# LMNC_VCO_-_v1_2.net
KiCad netlist of a schematic drawn in EAGLE
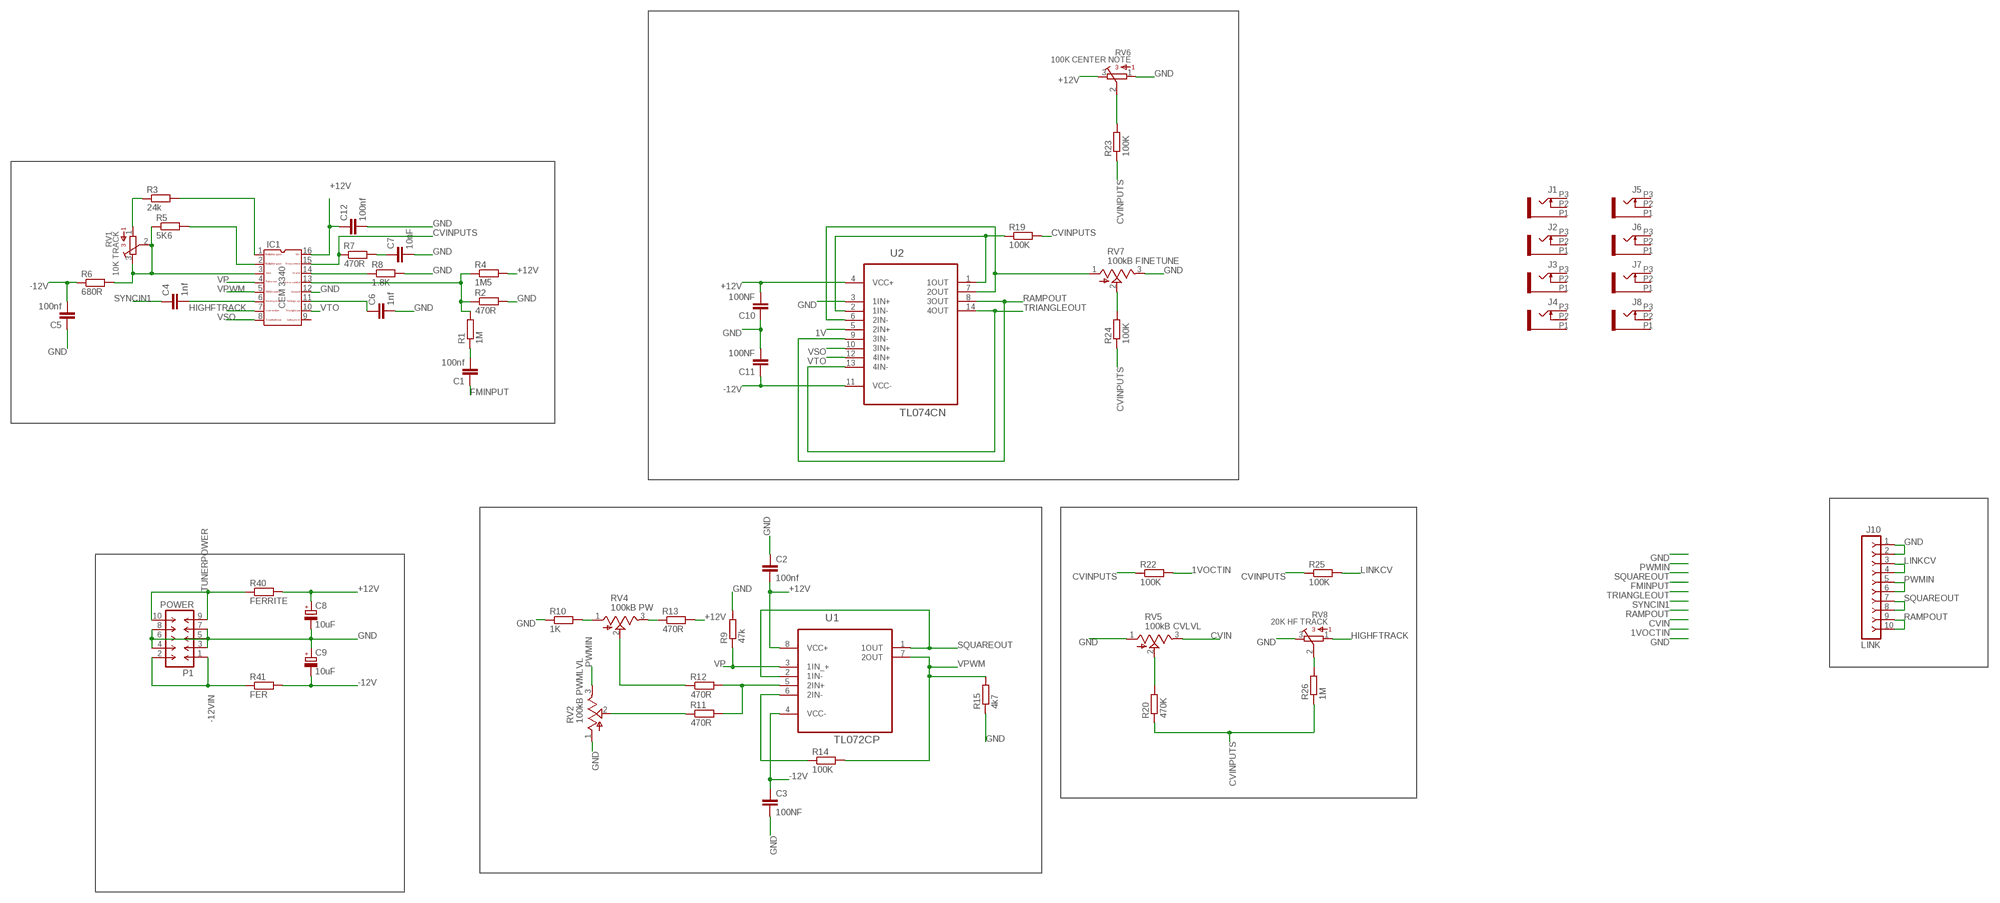
[diagram p0: schematic, sheet 1]

(export (version "E")
  (design (tool "Eeschema 10.0.6"))
  (components
    (comp (ref "C1")
      (value "100nf")
      (footprint "eagle-import:C0603")
      (libsource (lib "eagle-import") (part "C-EUC0603"))
    )
    (comp (ref "C2")
      (value "100nf")
      (footprint "eagle-import:C0603")
      (libsource (lib "eagle-import") (part "C-EUC0603"))
    )
    (comp (ref "C3")
      (value "100NF")
      (footprint "eagle-import:C0603")
      (libsource (lib "eagle-import") (part "C-EUC0603"))
    )
    (comp (ref "C4")
      (value "1nf")
      (footprint "eagle-import:C0603")
      (libsource (lib "eagle-import") (part "C-EUC0603"))
    )
    (comp (ref "C5")
      (value "100nf")
      (footprint "eagle-import:C0603")
      (libsource (lib "eagle-import") (part "C-EUC0603"))
    )
    (comp (ref "C6")
      (value "1nf")
      (footprint "eagle-import:C0603")
      (libsource (lib "eagle-import") (part "C-EUC0603"))
    )
    (comp (ref "C7")
      (value "10nF")
      (footprint "eagle-import:C0603")
      (libsource (lib "eagle-import") (part "C-EUC0603"))
    )
    (comp (ref "C8")
      (value "10uF")
      (footprint "eagle-import:153CLV-0605")
      (libsource (lib "eagle-import") (part "CPOL-EU153CLV-0605"))
    )
    (comp (ref "C9")
      (value "10uF")
      (footprint "eagle-import:153CLV-0605")
      (libsource (lib "eagle-import") (part "CPOL-EU153CLV-0605"))
    )
    (comp (ref "C10")
      (value "100NF")
      (footprint "eagle-import:C0603")
      (libsource (lib "eagle-import") (part "C-EUC0603"))
    )
    (comp (ref "C11")
      (value "100NF")
      (footprint "eagle-import:C0603")
      (libsource (lib "eagle-import") (part "C-EUC0603"))
    )
    (comp (ref "C12")
      (value "100nf")
      (footprint "eagle-import:C0603")
      (libsource (lib "eagle-import") (part "C-EUC0603"))
    )
    (comp (ref "IC1")
      (value "CEM3340")
      (footprint "eagle-import:DIL16")
      (libsource (lib "eagle-import") (part "CEM3340"))
    )
    (comp (ref "J1")
      (value "PJ301_THONKICONNTME")
      (footprint "eagle-import:WQP_PJ_301M_TME")
      (libsource (lib "eagle-import") (part "PJ301_THONKICONNTME"))
    )
    (comp (ref "J2")
      (value "PJ301_THONKICONNTME")
      (footprint "eagle-import:WQP_PJ_301M_TME")
      (libsource (lib "eagle-import") (part "PJ301_THONKICONNTME"))
    )
    (comp (ref "J3")
      (value "PJ301_THONKICONNTME")
      (footprint "eagle-import:WQP_PJ_301M_TME")
      (libsource (lib "eagle-import") (part "PJ301_THONKICONNTME"))
    )
    (comp (ref "J4")
      (value "PJ301_THONKICONNTME")
      (footprint "eagle-import:WQP_PJ_301M_TME")
      (libsource (lib "eagle-import") (part "PJ301_THONKICONNTME"))
    )
    (comp (ref "J5")
      (value "PJ301_THONKICONNTME")
      (footprint "eagle-import:WQP_PJ_301M_TME")
      (libsource (lib "eagle-import") (part "PJ301_THONKICONNTME"))
    )
    (comp (ref "J6")
      (value "PJ301_THONKICONNTME")
      (footprint "eagle-import:WQP_PJ_301M_TME")
      (libsource (lib "eagle-import") (part "PJ301_THONKICONNTME"))
    )
    (comp (ref "J7")
      (value "PJ301_THONKICONNTME")
      (footprint "eagle-import:WQP_PJ_301M_TME")
      (libsource (lib "eagle-import") (part "PJ301_THONKICONNTME"))
    )
    (comp (ref "J8")
      (value "PJ301_THONKICONNTME")
      (footprint "eagle-import:WQP_PJ_301M_TME")
      (libsource (lib "eagle-import") (part "PJ301_THONKICONNTME"))
    )
    (comp (ref "J10")
      (value "LINK")
      (footprint "eagle-import:SIP-100-10-32Y")
      (libsource (lib "eagle-import") (part "F-1X10-SIP-100-32Y"))
    )
    (comp (ref "P1")
      (value "POWER")
      (footprint "eagle-import:DIL-100-2X05")
      (libsource (lib "eagle-import") (part "M-2X05-DIL-100"))
    )
    (comp (ref "R1")
      (value "1M")
      (footprint "eagle-import:R0603")
      (libsource (lib "eagle-import") (part "R-EU_R0603"))
    )
    (comp (ref "R2")
      (value "470R")
      (footprint "eagle-import:R0603")
      (libsource (lib "eagle-import") (part "R-EU_R0603"))
    )
    (comp (ref "R3")
      (value "24k")
      (footprint "eagle-import:R0603")
      (libsource (lib "eagle-import") (part "R-EU_R0603"))
    )
    (comp (ref "R4")
      (value "1M5")
      (footprint "eagle-import:R0603")
      (libsource (lib "eagle-import") (part "R-EU_R0603"))
    )
    (comp (ref "R5")
      (value "5K6")
      (footprint "eagle-import:R0603")
      (libsource (lib "eagle-import") (part "R-EU_R0603"))
    )
    (comp (ref "R6")
      (value "680R")
      (footprint "eagle-import:R0603")
      (libsource (lib "eagle-import") (part "R-EU_R0603"))
    )
    (comp (ref "R7")
      (value "470R")
      (footprint "eagle-import:R0603")
      (libsource (lib "eagle-import") (part "R-EU_R0603"))
    )
    (comp (ref "R8")
      (value "1.8K")
      (footprint "eagle-import:R0603")
      (libsource (lib "eagle-import") (part "R-EU_R0603"))
    )
    (comp (ref "R9")
      (value "47k")
      (footprint "eagle-import:R0603")
      (libsource (lib "eagle-import") (part "R-EU_R0603"))
    )
    (comp (ref "R10")
      (value "1K")
      (footprint "eagle-import:R0603")
      (libsource (lib "eagle-import") (part "R-EU_R0603"))
    )
    (comp (ref "R11")
      (value "470R")
      (footprint "eagle-import:R0603")
      (libsource (lib "eagle-import") (part "R-EU_R0603"))
    )
    (comp (ref "R12")
      (value "470R")
      (footprint "eagle-import:R0603")
      (libsource (lib "eagle-import") (part "R-EU_R0603"))
    )
    (comp (ref "R13")
      (value "470R")
      (footprint "eagle-import:R0603")
      (libsource (lib "eagle-import") (part "R-EU_R0603"))
    )
    (comp (ref "R14")
      (value "100K")
      (footprint "eagle-import:R0603")
      (libsource (lib "eagle-import") (part "R-EU_R0603"))
    )
    (comp (ref "R15")
      (value "4k7")
      (footprint "eagle-import:R0603")
      (libsource (lib "eagle-import") (part "R-EU_R0603"))
    )
    (comp (ref "R19")
      (value "100K")
      (footprint "eagle-import:R0603")
      (libsource (lib "eagle-import") (part "R-EU_R0603"))
    )
    (comp (ref "R20")
      (value "470K")
      (footprint "eagle-import:R0603")
      (libsource (lib "eagle-import") (part "R-EU_R0603"))
    )
    (comp (ref "R22")
      (value "100K")
      (footprint "eagle-import:R0603")
      (libsource (lib "eagle-import") (part "R-EU_R0603"))
    )
    (comp (ref "R23")
      (value "100K")
      (footprint "eagle-import:R0603")
      (libsource (lib "eagle-import") (part "R-EU_R0603"))
    )
    (comp (ref "R24")
      (value "100K")
      (footprint "eagle-import:R0603")
      (libsource (lib "eagle-import") (part "R-EU_R0603"))
    )
    (comp (ref "R25")
      (value "100K")
      (footprint "eagle-import:R0603")
      (libsource (lib "eagle-import") (part "R-EU_R0603"))
    )
    (comp (ref "R26")
      (value "1M")
      (footprint "eagle-import:R0603")
      (libsource (lib "eagle-import") (part "R-EU_R0603"))
    )
    (comp (ref "R40")
      (value "FERRITE")
      (footprint "eagle-import:R0603")
      (libsource (lib "eagle-import") (part "R-EU_R0603"))
    )
    (comp (ref "R41")
      (value "FER")
      (footprint "eagle-import:R0603")
      (libsource (lib "eagle-import") (part "R-EU_R0603"))
    )
    (comp (ref "RV1")
      (value "10K TRACK")
      (footprint "eagle-import:3386W")
      (libsource (lib "eagle-import") (part "3386-W"))
    )
    (comp (ref "RV2")
      (value "100kB PWMLVL")
      (footprint "eagle-import:ALPS_POT_VERTICAL")
      (libsource (lib "eagle-import") (part "POT_VERTICAL"))
    )
    (comp (ref "RV4")
      (value "100kB PW")
      (footprint "eagle-import:ALPS_POT_VERTICAL")
      (libsource (lib "eagle-import") (part "POT_VERTICAL"))
    )
    (comp (ref "RV5")
      (value "100kB CVLVL")
      (footprint "eagle-import:ALPS_POT_VERTICAL")
      (libsource (lib "eagle-import") (part "POT_VERTICAL"))
    )
    (comp (ref "RV6")
      (value "100K CENTER NOTE")
      (footprint "eagle-import:3386W")
      (libsource (lib "eagle-import") (part "3386-W"))
    )
    (comp (ref "RV7")
      (value "100kB FINETUNE")
      (footprint "eagle-import:ALPS_POT_VERTICAL")
      (libsource (lib "eagle-import") (part "POT_VERTICAL"))
    )
    (comp (ref "RV8")
      (value "20K HF TRACK")
      (footprint "eagle-import:3386W")
      (libsource (lib "eagle-import") (part "3386-W"))
    )
    (comp (ref "U1")
      (value "TL072CP")
      (footprint "eagle-import:DIP254P762X508-8")
      (fields (field (name "MF") "Texas Instruments"))
      (libsource (lib "eagle-import") (part "TL072CP"))
    )
    (comp (ref "U2")
      (value "TL074CN")
      (footprint "eagle-import:DIP254P762X508-14")
      (fields (field (name "MF") "STMicroelectronics"))
      (libsource (lib "eagle-import") (part "TL074CN"))
    )
  )
  (nets
    (net (code "1") (name "+12V") (class "Default")
      (node (ref "C10") (pin "2") (pinfunction "2_2") (pintype "passive"))
      (node (ref "C12") (pin "1") (pinfunction "1_1") (pintype "passive"))
      (node (ref "C2") (pin "2") (pinfunction "2_2") (pintype "passive"))
      (node (ref "C8") (pin "+") (pinfunction "+_+") (pintype "passive"))
      (node (ref "IC1") (pin "16") (pinfunction "16_16") (pintype "power_in"))
      (node (ref "R13") (pin "2") (pinfunction "2_2") (pintype "passive"))
      (node (ref "R4") (pin "2") (pinfunction "2_2") (pintype "passive"))
      (node (ref "R40") (pin "2") (pinfunction "2_2") (pintype "passive"))
      (node (ref "RV6") (pin "3") (pinfunction "3_3") (pintype "passive"))
      (node (ref "U1") (pin "8") (pinfunction "VCC+_8") (pintype "power_in"))
      (node (ref "U2") (pin "4") (pinfunction "VCC+_4") (pintype "power_in"))
    )
    (net (code "2") (name "-12V") (class "Default")
      (node (ref "C11") (pin "1") (pinfunction "1_1") (pintype "passive"))
      (node (ref "C3") (pin "1") (pinfunction "1_1") (pintype "passive"))
      (node (ref "C5") (pin "2") (pinfunction "2_2") (pintype "passive"))
      (node (ref "C9") (pin "-") (pinfunction "-_-") (pintype "passive"))
      (node (ref "R41") (pin "2") (pinfunction "2_2") (pintype "passive"))
      (node (ref "R6") (pin "1") (pinfunction "1_1") (pintype "passive"))
      (node (ref "U1") (pin "4") (pinfunction "VCC-_4") (pintype "passive"))
      (node (ref "U2") (pin "11") (pinfunction "VCC-_11") (pintype "power_in"))
    )
    (net (code "3") (name "-12VIN") (class "Default")
      (node (ref "P1") (pin "1") (pinfunction "1_1") (pintype "passive"))
      (node (ref "P1") (pin "2") (pinfunction "2_2") (pintype "passive"))
      (node (ref "R41") (pin "1") (pinfunction "1_1") (pintype "passive"))
    )
    (net (code "4") (name "1V") (class "Default")
      (node (ref "U2") (pin "5") (pinfunction "2IN+_5") (pintype "input"))
    )
    (net (code "5") (name "1VOCTIN") (class "Default")
      (node (ref "R22") (pin "2") (pinfunction "2_2") (pintype "passive"))
    )
    (net (code "6") (name "CVIN") (class "Default")
      (node (ref "RV5") (pin "3") (pinfunction "B_3") (pintype "passive"))
    )
    (net (code "7") (name "CVINPUTS") (class "Default")
      (node (ref "IC1") (pin "15") (pinfunction "15_15") (pintype "input"))
      (node (ref "R19") (pin "2") (pinfunction "2_2") (pintype "passive"))
      (node (ref "R20") (pin "1") (pinfunction "1_1") (pintype "passive"))
      (node (ref "R22") (pin "1") (pinfunction "1_1") (pintype "passive"))
      (node (ref "R23") (pin "1") (pinfunction "1_1") (pintype "passive"))
      (node (ref "R24") (pin "1") (pinfunction "1_1") (pintype "passive"))
      (node (ref "R25") (pin "1") (pinfunction "1_1") (pintype "passive"))
      (node (ref "R26") (pin "1") (pinfunction "1_1") (pintype "passive"))
      (node (ref "R7") (pin "1") (pinfunction "1_1") (pintype "passive"))
    )
    (net (code "8") (name "FMINPUT") (class "Default")
      (node (ref "C1") (pin "1") (pinfunction "1_1") (pintype "passive"))
    )
    (net (code "9") (name "GND") (class "Default")
      (node (ref "C10") (pin "1") (pinfunction "1_1") (pintype "passive"))
      (node (ref "C11") (pin "2") (pinfunction "2_2") (pintype "passive"))
      (node (ref "C12") (pin "2") (pinfunction "2_2") (pintype "passive"))
      (node (ref "C2") (pin "1") (pinfunction "1_1") (pintype "passive"))
      (node (ref "C3") (pin "2") (pinfunction "2_2") (pintype "passive"))
      (node (ref "C5") (pin "1") (pinfunction "1_1") (pintype "passive"))
      (node (ref "C6") (pin "2") (pinfunction "2_2") (pintype "passive"))
      (node (ref "C7") (pin "2") (pinfunction "2_2") (pintype "passive"))
      (node (ref "C8") (pin "-") (pinfunction "-_-") (pintype "passive"))
      (node (ref "C9") (pin "+") (pinfunction "+_+") (pintype "passive"))
      (node (ref "IC1") (pin "12") (pinfunction "12_12") (pintype "power_in"))
      (node (ref "J10") (pin "1") (pinfunction "1_1") (pintype "passive"))
      (node (ref "J10") (pin "2") (pinfunction "2_2") (pintype "passive"))
      (node (ref "P1") (pin "3") (pinfunction "3_3") (pintype "passive"))
      (node (ref "P1") (pin "4") (pinfunction "4_4") (pintype "passive"))
      (node (ref "P1") (pin "5") (pinfunction "5_5") (pintype "passive"))
      (node (ref "P1") (pin "6") (pinfunction "6_6") (pintype "passive"))
      (node (ref "P1") (pin "7") (pinfunction "7_7") (pintype "passive"))
      (node (ref "P1") (pin "8") (pinfunction "8_8") (pintype "passive"))
      (node (ref "R10") (pin "1") (pinfunction "1_1") (pintype "passive"))
      (node (ref "R15") (pin "1") (pinfunction "1_1") (pintype "passive"))
      (node (ref "R2") (pin "2") (pinfunction "2_2") (pintype "passive"))
      (node (ref "R8") (pin "2") (pinfunction "2_2") (pintype "passive"))
      (node (ref "R9") (pin "2") (pinfunction "2_2") (pintype "passive"))
      (node (ref "RV2") (pin "1") (pinfunction "A_1") (pintype "passive"))
      (node (ref "RV5") (pin "1") (pinfunction "A_1") (pintype "passive"))
      (node (ref "RV6") (pin "1") (pinfunction "1_1") (pintype "passive"))
      (node (ref "RV7") (pin "3") (pinfunction "B_3") (pintype "passive"))
      (node (ref "RV8") (pin "3") (pinfunction "3_3") (pintype "passive"))
      (node (ref "U2") (pin "3") (pinfunction "1IN+_3") (pintype "input"))
    )
    (net (code "10") (name "HIGHFTRACK") (class "Default")
      (node (ref "IC1") (pin "7") (pinfunction "7_7") (pintype "bidirectional"))
      (node (ref "RV8") (pin "1") (pinfunction "1_1") (pintype "passive"))
    )
    (net (code "11") (name "LINKCV") (class "Default")
      (node (ref "J10") (pin "3") (pinfunction "3_3") (pintype "passive"))
      (node (ref "J10") (pin "4") (pinfunction "4_4") (pintype "passive"))
      (node (ref "R25") (pin "2") (pinfunction "2_2") (pintype "passive"))
    )
    (net (code "12") (name "Net-(C1-Pad2)") (class "Default")
      (node (ref "C1") (pin "2") (pinfunction "2_2") (pintype "passive"))
      (node (ref "R1") (pin "1") (pinfunction "1_1") (pintype "passive"))
    )
    (net (code "13") (name "Net-(C4-Pad2)") (class "Default")
      (node (ref "C4") (pin "2") (pinfunction "2_2") (pintype "passive"))
      (node (ref "IC1") (pin "6") (pinfunction "6_6") (pintype "input"))
    )
    (net (code "14") (name "Net-(C6-Pad1)") (class "Default")
      (node (ref "C6") (pin "1") (pinfunction "1_1") (pintype "passive"))
      (node (ref "IC1") (pin "11") (pinfunction "11_11") (pintype "bidirectional"))
    )
    (net (code "15") (name "Net-(C7-Pad1)") (class "Default")
      (node (ref "C7") (pin "1") (pinfunction "1_1") (pintype "passive"))
      (node (ref "R7") (pin "2") (pinfunction "2_2") (pintype "passive"))
    )
    (net (code "16") (name "Net-(IC1-Pad1)") (class "Default")
      (node (ref "IC1") (pin "1") (pinfunction "1_1") (pintype "bidirectional"))
      (node (ref "R3") (pin "2") (pinfunction "2_2") (pintype "passive"))
    )
    (net (code "17") (name "Net-(IC1-Pad2)") (class "Default")
      (node (ref "IC1") (pin "2") (pinfunction "2_2") (pintype "bidirectional"))
      (node (ref "R5") (pin "2") (pinfunction "2_2") (pintype "passive"))
    )
    (net (code "18") (name "Net-(IC1-Pad3)") (class "Default")
      (node (ref "IC1") (pin "3") (pinfunction "3_3") (pintype "power_in"))
      (node (ref "R5") (pin "1") (pinfunction "1_1") (pintype "passive"))
      (node (ref "R6") (pin "2") (pinfunction "2_2") (pintype "passive"))
      (node (ref "RV1") (pin "2") (pinfunction "2_2") (pintype "passive"))
      (node (ref "RV1") (pin "3") (pinfunction "3_3") (pintype "passive"))
    )
    (net (code "19") (name "Net-(IC1-Pad13)") (class "Default")
      (node (ref "IC1") (pin "13") (pinfunction "13_13") (pintype "input"))
      (node (ref "R1") (pin "2") (pinfunction "2_2") (pintype "passive"))
      (node (ref "R2") (pin "1") (pinfunction "1_1") (pintype "passive"))
      (node (ref "R4") (pin "1") (pinfunction "1_1") (pintype "passive"))
    )
    (net (code "20") (name "Net-(IC1-Pad14)") (class "Default")
      (node (ref "IC1") (pin "14") (pinfunction "14_14") (pintype "input"))
      (node (ref "R8") (pin "1") (pinfunction "1_1") (pintype "passive"))
    )
    (net (code "21") (name "Net-(R3-Pad1)") (class "Default")
      (node (ref "R3") (pin "1") (pinfunction "1_1") (pintype "passive"))
      (node (ref "RV1") (pin "1") (pinfunction "1_1") (pintype "passive"))
    )
    (net (code "22") (name "Net-(R23-Pad2)") (class "Default")
      (node (ref "R23") (pin "2") (pinfunction "2_2") (pintype "passive"))
      (node (ref "RV6") (pin "2") (pinfunction "2_2") (pintype "passive"))
    )
    (net (code "23") (name "Net-(R26-Pad2)") (class "Default")
      (node (ref "R26") (pin "2") (pinfunction "2_2") (pintype "passive"))
      (node (ref "RV8") (pin "2") (pinfunction "2_2") (pintype "passive"))
    )
    (net (code "24") (name "Net-(RV2-W)") (class "Default")
      (node (ref "R11") (pin "1") (pinfunction "1_1") (pintype "passive"))
      (node (ref "RV2") (pin "2") (pinfunction "W_2") (pintype "passive"))
    )
    (net (code "25") (name "Net-(RV4-A)") (class "Default")
      (node (ref "R10") (pin "2") (pinfunction "2_2") (pintype "passive"))
      (node (ref "RV4") (pin "1") (pinfunction "A_1") (pintype "passive"))
    )
    (net (code "26") (name "Net-(RV4-B)") (class "Default")
      (node (ref "R13") (pin "1") (pinfunction "1_1") (pintype "passive"))
      (node (ref "RV4") (pin "3") (pinfunction "B_3") (pintype "passive"))
    )
    (net (code "27") (name "Net-(RV4-W)") (class "Default")
      (node (ref "R12") (pin "1") (pinfunction "1_1") (pintype "passive"))
      (node (ref "RV4") (pin "2") (pinfunction "W_2") (pintype "passive"))
    )
    (net (code "28") (name "Net-(RV5-W)") (class "Default")
      (node (ref "R20") (pin "2") (pinfunction "2_2") (pintype "passive"))
      (node (ref "RV5") (pin "2") (pinfunction "W_2") (pintype "passive"))
    )
    (net (code "29") (name "Net-(RV7-A)") (class "Default")
      (node (ref "RV7") (pin "1") (pinfunction "A_1") (pintype "passive"))
      (node (ref "U2") (pin "6") (pinfunction "2IN-_6") (pintype "input"))
      (node (ref "U2") (pin "7") (pinfunction "2OUT_7") (pintype "output"))
    )
    (net (code "30") (name "Net-(RV7-W)") (class "Default")
      (node (ref "R24") (pin "2") (pinfunction "2_2") (pintype "passive"))
      (node (ref "RV7") (pin "2") (pinfunction "W_2") (pintype "passive"))
    )
    (net (code "31") (name "Net-(U1-2IN+)") (class "Default")
      (node (ref "R11") (pin "2") (pinfunction "2_2") (pintype "passive"))
      (node (ref "R12") (pin "2") (pinfunction "2_2") (pintype "passive"))
      (node (ref "U1") (pin "5") (pinfunction "2IN+_5") (pintype "input"))
    )
    (net (code "32") (name "Net-(U1-2IN-)") (class "Default")
      (node (ref "R14") (pin "1") (pinfunction "1_1") (pintype "passive"))
      (node (ref "U1") (pin "6") (pinfunction "2IN-_6") (pintype "input"))
    )
    (net (code "33") (name "Net-(U2-1IN-)") (class "Default")
      (node (ref "R19") (pin "1") (pinfunction "1_1") (pintype "passive"))
      (node (ref "U2") (pin "1") (pinfunction "1OUT_1") (pintype "output"))
      (node (ref "U2") (pin "2") (pinfunction "1IN-_2") (pintype "input"))
    )
    (net (code "34") (name "PWMIN") (class "Default")
      (node (ref "J10") (pin "5") (pinfunction "5_5") (pintype "passive"))
      (node (ref "J10") (pin "6") (pinfunction "6_6") (pintype "passive"))
      (node (ref "RV2") (pin "3") (pinfunction "B_3") (pintype "passive"))
    )
    (net (code "35") (name "RAMPOUT") (class "Default")
      (node (ref "J10") (pin "10") (pinfunction "10_10") (pintype "passive"))
      (node (ref "J10") (pin "9") (pinfunction "9_9") (pintype "passive"))
      (node (ref "U2") (pin "8") (pinfunction "3OUT_8") (pintype "output"))
      (node (ref "U2") (pin "9") (pinfunction "3IN-_9") (pintype "input"))
    )
    (net (code "36") (name "SQUAREOUT") (class "Default")
      (node (ref "J10") (pin "7") (pinfunction "7_7") (pintype "passive"))
      (node (ref "J10") (pin "8") (pinfunction "8_8") (pintype "passive"))
      (node (ref "U1") (pin "1") (pinfunction "1OUT_1") (pintype "output"))
      (node (ref "U1") (pin "2") (pinfunction "1IN-_2") (pintype "input"))
    )
    (net (code "37") (name "SYNCIN1") (class "Default")
      (node (ref "C4") (pin "1") (pinfunction "1_1") (pintype "passive"))
    )
    (net (code "38") (name "TRIANGLEOUT") (class "Default")
      (node (ref "U2") (pin "13") (pinfunction "4IN-_13") (pintype "input"))
      (node (ref "U2") (pin "14") (pinfunction "4OUT_14") (pintype "output"))
    )
    (net (code "39") (name "TUNERPOWER") (class "Default")
      (node (ref "P1") (pin "10") (pinfunction "10_10") (pintype "passive"))
      (node (ref "P1") (pin "9") (pinfunction "9_9") (pintype "passive"))
      (node (ref "R40") (pin "1") (pinfunction "1_1") (pintype "passive"))
    )
    (net (code "40") (name "VP") (class "Default")
      (node (ref "IC1") (pin "4") (pinfunction "4_4") (pintype "output"))
      (node (ref "R9") (pin "1") (pinfunction "1_1") (pintype "passive"))
      (node (ref "U1") (pin "3") (pinfunction "1IN_+_3") (pintype "input"))
    )
    (net (code "41") (name "VPWM") (class "Default")
      (node (ref "IC1") (pin "5") (pinfunction "5_5") (pintype "input"))
      (node (ref "R14") (pin "2") (pinfunction "2_2") (pintype "passive"))
      (node (ref "R15") (pin "2") (pinfunction "2_2") (pintype "passive"))
      (node (ref "U1") (pin "7") (pinfunction "2OUT_7") (pintype "output"))
    )
    (net (code "42") (name "VSO") (class "Default")
      (node (ref "IC1") (pin "8") (pinfunction "8_8") (pintype "output"))
      (node (ref "U2") (pin "10") (pinfunction "3IN+_10") (pintype "input"))
    )
    (net (code "43") (name "VTO") (class "Default")
      (node (ref "IC1") (pin "10") (pinfunction "10_10") (pintype "output"))
      (node (ref "U2") (pin "12") (pinfunction "4IN+_12") (pintype "input"))
    )
    (net (code "44") (name "unconnected-(IC1-Pad9)") (class "Default")
      (node (ref "IC1") (pin "9") (pinfunction "9_9") (pintype "input"))
    )
    (net (code "45") (name "unconnected-(J1-1-PadP1)") (class "Default")
      (node (ref "J1") (pin "P1") (pinfunction "1_P1") (pintype "passive"))
    )
    (net (code "46") (name "unconnected-(J1-2-PadP2)") (class "Default")
      (node (ref "J1") (pin "P2") (pinfunction "2_P2") (pintype "passive"))
    )
    (net (code "47") (name "unconnected-(J1-3-PadP3)") (class "Default")
      (node (ref "J1") (pin "P3") (pinfunction "3_P3") (pintype "passive"))
    )
    (net (code "48") (name "unconnected-(J2-1-PadP1)") (class "Default")
      (node (ref "J2") (pin "P1") (pinfunction "1_P1") (pintype "passive"))
    )
    (net (code "49") (name "unconnected-(J2-2-PadP2)") (class "Default")
      (node (ref "J2") (pin "P2") (pinfunction "2_P2") (pintype "passive"))
    )
    (net (code "50") (name "unconnected-(J2-3-PadP3)") (class "Default")
      (node (ref "J2") (pin "P3") (pinfunction "3_P3") (pintype "passive"))
    )
    (net (code "51") (name "unconnected-(J3-1-PadP1)") (class "Default")
      (node (ref "J3") (pin "P1") (pinfunction "1_P1") (pintype "passive"))
    )
    (net (code "52") (name "unconnected-(J3-2-PadP2)") (class "Default")
      (node (ref "J3") (pin "P2") (pinfunction "2_P2") (pintype "passive"))
    )
    (net (code "53") (name "unconnected-(J3-3-PadP3)") (class "Default")
      (node (ref "J3") (pin "P3") (pinfunction "3_P3") (pintype "passive"))
    )
    (net (code "54") (name "unconnected-(J4-1-PadP1)") (class "Default")
      (node (ref "J4") (pin "P1") (pinfunction "1_P1") (pintype "passive"))
    )
    (net (code "55") (name "unconnected-(J4-2-PadP2)") (class "Default")
      (node (ref "J4") (pin "P2") (pinfunction "2_P2") (pintype "passive"))
    )
    (net (code "56") (name "unconnected-(J4-3-PadP3)") (class "Default")
      (node (ref "J4") (pin "P3") (pinfunction "3_P3") (pintype "passive"))
    )
    (net (code "57") (name "unconnected-(J5-1-PadP1)") (class "Default")
      (node (ref "J5") (pin "P1") (pinfunction "1_P1") (pintype "passive"))
    )
    (net (code "58") (name "unconnected-(J5-2-PadP2)") (class "Default")
      (node (ref "J5") (pin "P2") (pinfunction "2_P2") (pintype "passive"))
    )
    (net (code "59") (name "unconnected-(J5-3-PadP3)") (class "Default")
      (node (ref "J5") (pin "P3") (pinfunction "3_P3") (pintype "passive"))
    )
    (net (code "60") (name "unconnected-(J6-1-PadP1)") (class "Default")
      (node (ref "J6") (pin "P1") (pinfunction "1_P1") (pintype "passive"))
    )
    (net (code "61") (name "unconnected-(J6-2-PadP2)") (class "Default")
      (node (ref "J6") (pin "P2") (pinfunction "2_P2") (pintype "passive"))
    )
    (net (code "62") (name "unconnected-(J6-3-PadP3)") (class "Default")
      (node (ref "J6") (pin "P3") (pinfunction "3_P3") (pintype "passive"))
    )
    (net (code "63") (name "unconnected-(J7-1-PadP1)") (class "Default")
      (node (ref "J7") (pin "P1") (pinfunction "1_P1") (pintype "passive"))
    )
    (net (code "64") (name "unconnected-(J7-2-PadP2)") (class "Default")
      (node (ref "J7") (pin "P2") (pinfunction "2_P2") (pintype "passive"))
    )
    (net (code "65") (name "unconnected-(J7-3-PadP3)") (class "Default")
      (node (ref "J7") (pin "P3") (pinfunction "3_P3") (pintype "passive"))
    )
    (net (code "66") (name "unconnected-(J8-1-PadP1)") (class "Default")
      (node (ref "J8") (pin "P1") (pinfunction "1_P1") (pintype "passive"))
    )
    (net (code "67") (name "unconnected-(J8-2-PadP2)") (class "Default")
      (node (ref "J8") (pin "P2") (pinfunction "2_P2") (pintype "passive"))
    )
    (net (code "68") (name "unconnected-(J8-3-PadP3)") (class "Default")
      (node (ref "J8") (pin "P3") (pinfunction "3_P3") (pintype "passive"))
    )
  )
)
